# LCD_FRIDA.net
KiCad netlist of a schematic drawn in Altium Designer
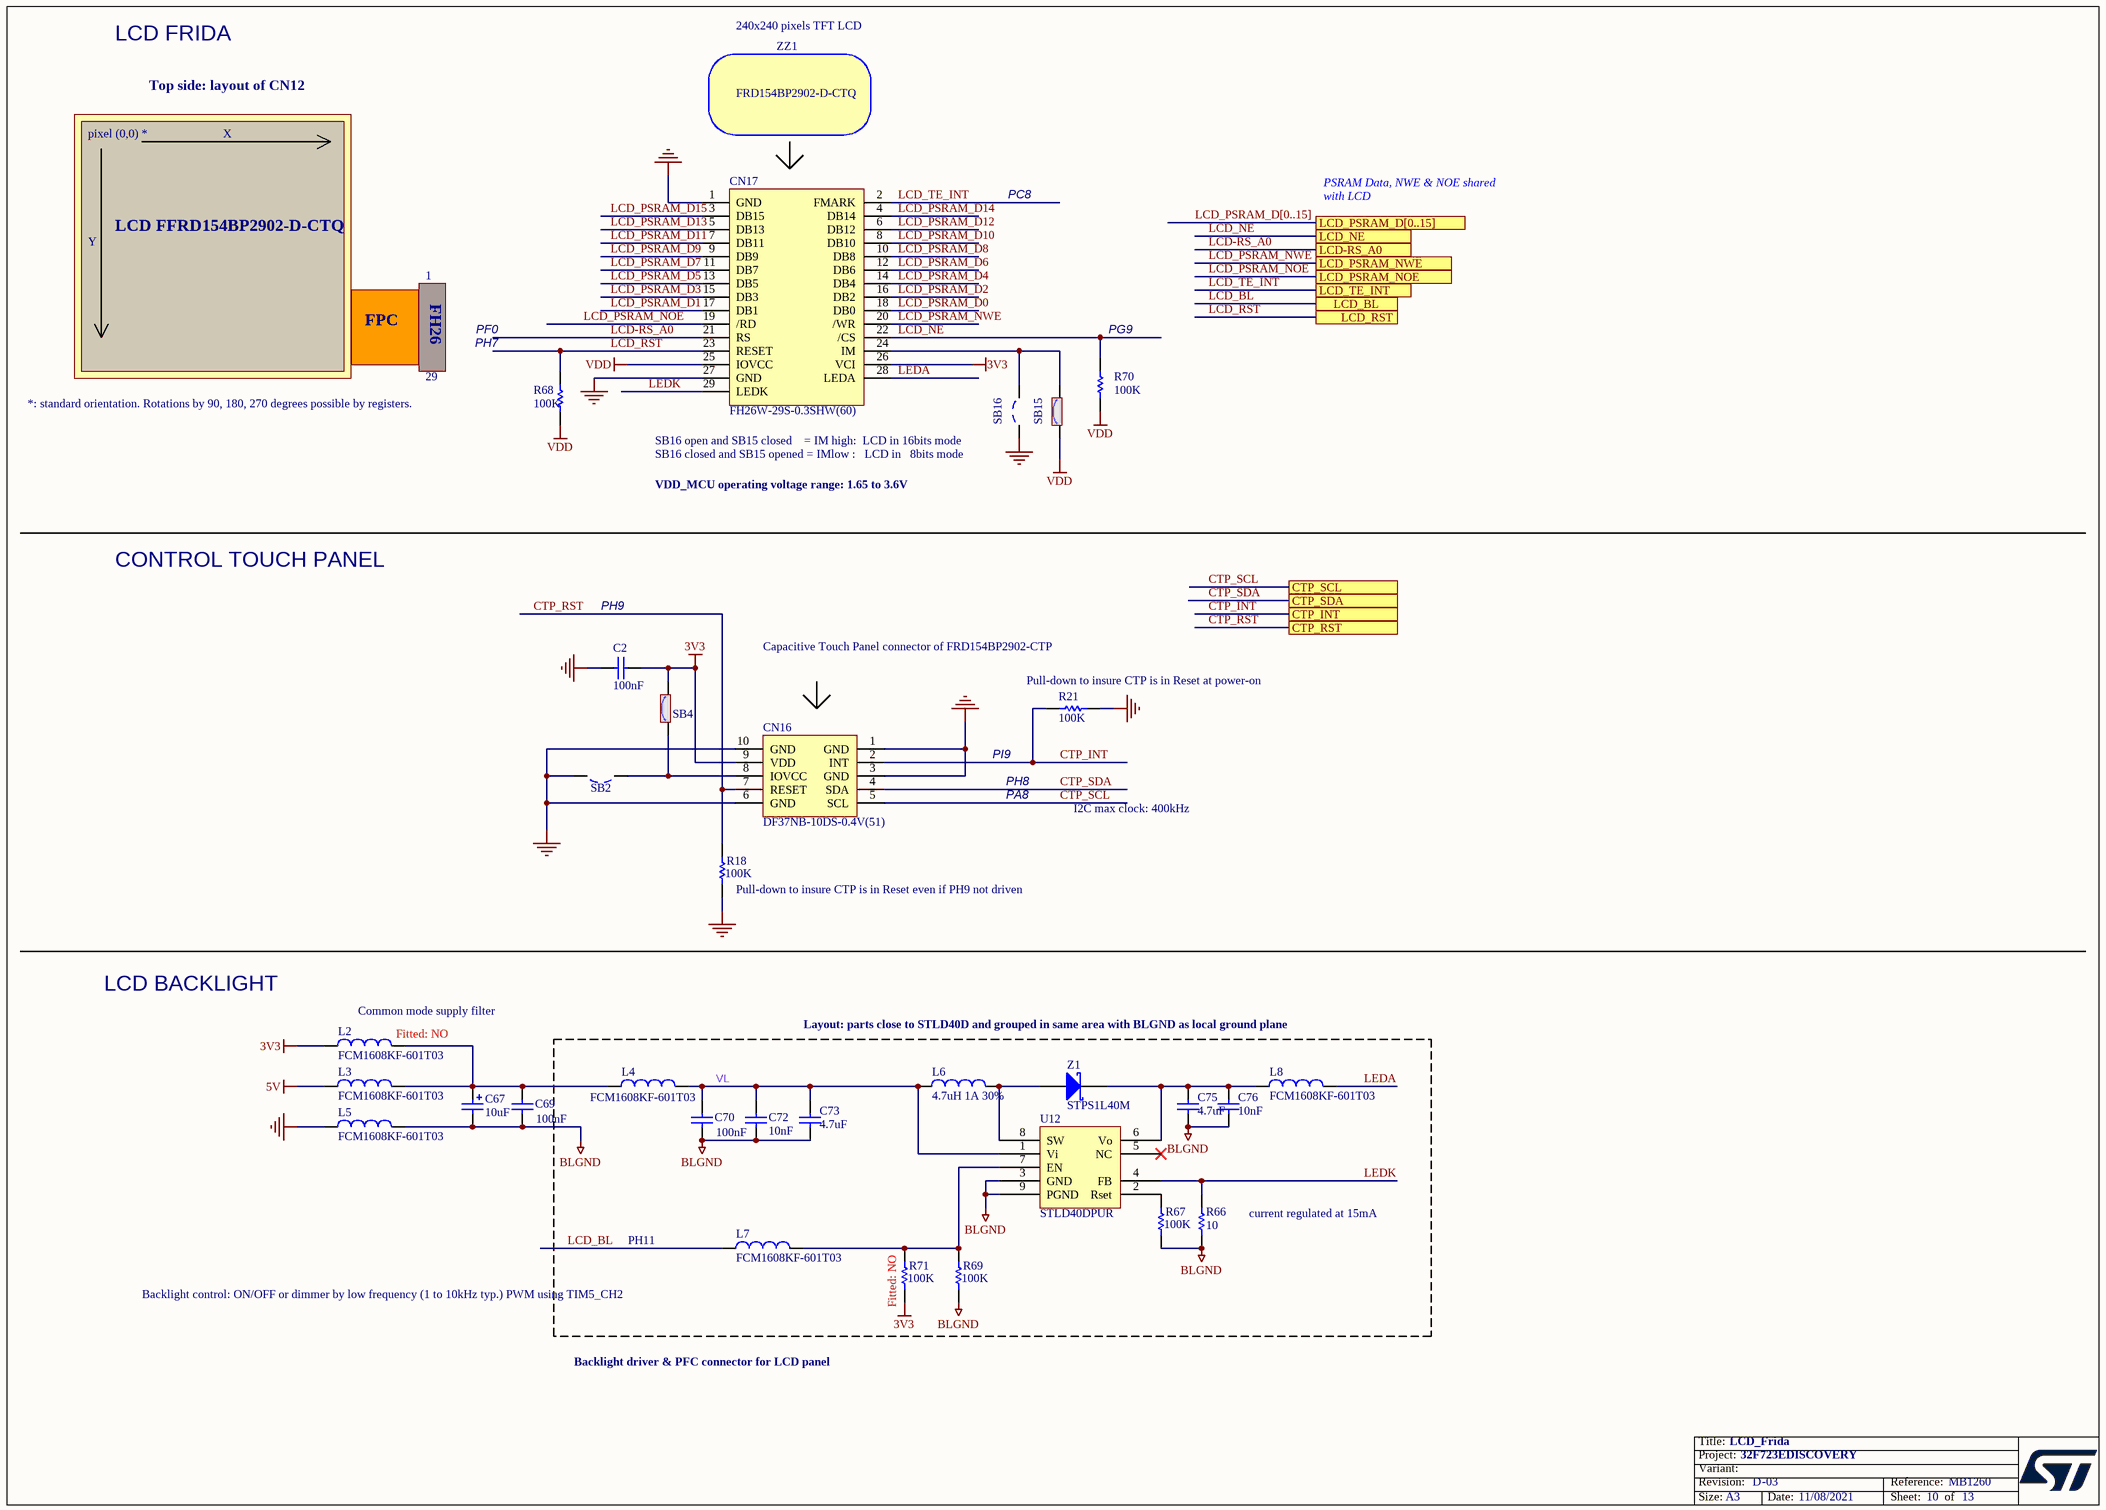
[diagram p0: LCD_FRIDA.SchDoc]

(export (version "E")
  (design (tool "Eeschema 10.0.6"))
  (components
    (comp (ref "C2")
      (value "100nF")
      (footprint "0402C")
      (description "Capacitor,100nF,16V,X7R,10%,0402,YAGEO")
      (libsource (lib "MCD_TOOLS") (part "Cap_100nF_X7R_10%_0402"))
    )
    (comp (ref "C67")
      (value "10uF")
      (footprint "TAN-A")
      (description "Polarized Capacitor,10uF,10V,10%,typeA,VISHAY")
      (fields (field (name "Comment") "10uF_POL_10%_TANA"))
      (libsource (lib "MCD_TOOLS_CAPACITOR") (part "Cap_10uF_POL_10%_TANA"))
    )
    (comp (ref "C69")
      (value "100nF")
      (footprint "0402C")
      (description "Capacitor,100nF,16V,X7R,10%,0402,YAGEO")
      (libsource (lib "MCD_TOOLS") (part "Cap_100nF_X7R_10%_0402"))
    )
    (comp (ref "C70")
      (value "100nF")
      (footprint "0402C")
      (description "Capacitor,100nF,16V,X7R,10%,0402,YAGEO")
      (libsource (lib "MCD_TOOLS") (part "Cap_100nF_X7R_10%_0402"))
    )
    (comp (ref "C72")
      (value "10nF")
      (footprint "0603C")
      (description "Capacitor,10nF,50V,X7R,10%,0603,YAGEO")
      (fields (field (name "Comment") "10nF_X7R_10%_0603"))
      (libsource (lib "MCD_TOOLS_CAPACITOR") (part "Cap_10nF_X7R_10%_0603"))
    )
    (comp (ref "C73")
      (value "4.7uF")
      (footprint "1206C")
      (description "Capacitor,4.7uF,50V, X7R,10%,1206,AVX")
      (fields (field (name "Comment") "4.7uF_X7R_10%_1206"))
      (libsource (lib "MCD_TOOLS_CAPACITOR") (part "Cap_4.7uF_X7R_10%_1206"))
    )
    (comp (ref "C75")
      (value "4.7uF")
      (footprint "1206C")
      (description "Capacitor,4.7uF,50V, X7R,10%,1206,AVX")
      (fields (field (name "Comment") "4.7uF_X7R_10%_1206"))
      (libsource (lib "MCD_TOOLS_CAPACITOR") (part "Cap_4.7uF_X7R_10%_1206"))
    )
    (comp (ref "C76")
      (value "10nF")
      (footprint "0603C")
      (description "Capacitor,10nF,50V,X7R,10%,0603,YAGEO")
      (fields (field (name "Comment") "10nF_X7R_10%_0603"))
      (libsource (lib "MCD_TOOLS_CAPACITOR") (part "Cap_10nF_X7R_10%_0603"))
    )
    (comp (ref "CN16")
      (value "DF37NB-10DS-0.4V(51)")
      (footprint "DF37NB-10DS-0R4V")
      (description "Header, 5-Pin, Dual row")
      (fields (field (name "PUBLISHER") "Altium Limited"))
      (libsource (lib "MB1209") (part "Header 5X2A"))
    )
    (comp (ref "CN17")
      (value "FH26W-29S-0.3SHW(60)")
      (footprint "FH26-29S-0R3SHW")
      (description "29pins FPC connector")
      (libsource (lib "MCD_TEMP_NPA") (part "FH26-29S-0.3SHW"))
    )
    (comp (ref "L2")
      (value "FCM1608KF-601T03")
      (footprint "0603L")
      (description "Bead,600R,350mA,0603,FCM1608KF-601T03,Tai-tech")
      (fields (field (name "FITTED") "NO"))
      (libsource (lib "MCD_TOOLS_MISCELLANEOUS") (part "BEAD_600R_350MA_0603"))
    )
    (comp (ref "L3")
      (value "FCM1608KF-601T03")
      (footprint "0603L")
      (description "Bead,600R,350mA,0603,FCM1608KF-601T03,Tai-tech")
      (libsource (lib "MCD_TOOLS_MISCELLANEOUS") (part "BEAD_600R_350MA_0603"))
    )
    (comp (ref "L4")
      (value "FCM1608KF-601T03")
      (footprint "0603L")
      (description "Bead,600R,350mA,0603,FCM1608KF-601T03,Tai-tech")
      (libsource (lib "MCD_TOOLS_MISCELLANEOUS") (part "BEAD_600R_350MA_0603"))
    )
    (comp (ref "L5")
      (value "FCM1608KF-601T03")
      (footprint "0603L")
      (description "Bead,600R,350mA,0603,FCM1608KF-601T03,Tai-tech")
      (libsource (lib "MCD_TOOLS_MISCELLANEOUS") (part "BEAD_600R_350MA_0603"))
    )
    (comp (ref "L6")
      (value "4.7uH 1A 30%")
      (footprint "1210L")
      (description "FIXED IND 4.7UH 1A 180 MOHM 30% SMD")
      (libsource (lib "MCD_TOOLS_MISCELLANEOUS") (part "Ind_4.7uH_1A_30%"))
    )
    (comp (ref "L7")
      (value "FCM1608KF-601T03")
      (footprint "0603L")
      (description "Bead,600R,350mA,0603,FCM1608KF-601T03,Tai-tech")
      (libsource (lib "MCD_TOOLS_MISCELLANEOUS") (part "BEAD_600R_350MA_0603"))
    )
    (comp (ref "L8")
      (value "FCM1608KF-601T03")
      (footprint "0603L")
      (description "Bead,600R,350mA,0603,FCM1608KF-601T03,Tai-tech")
      (libsource (lib "MCD_TOOLS_MISCELLANEOUS") (part "BEAD_600R_350MA_0603"))
    )
    (comp (ref "R18")
      (value "100K")
      (footprint "0402R")
      (description "Resistor,100K,0402,1%,YAGEO")
      (fields (field (name "Comment") "100K_1%_0402"))
      (libsource (lib "MCD_TOOLS_RESISTOR") (part "Res_100K_1%_0402"))
    )
    (comp (ref "R21")
      (value "100K")
      (footprint "0402R")
      (description "Resistor,100K,0402,1%,YAGEO")
      (fields (field (name "Comment") "100K_1%_0402"))
      (libsource (lib "MCD_TOOLS_RESISTOR") (part "Res_100K_1%_0402"))
    )
    (comp (ref "R66")
      (value "10")
      (footprint "0603R")
      (description "Resistor,10,0603,1%,ROHM,1/4W")
      (fields (field (name "Comment") "10_1%_0603"))
      (libsource (lib "MCD_TOOLS_RESISTOR") (part "Res_10_1%_0603"))
    )
    (comp (ref "R67")
      (value "100K")
      (footprint "0402R")
      (description "Resistor,100K,0402,1%,YAGEO")
      (fields (field (name "Comment") "100K_1%_0402"))
      (libsource (lib "MCD_TOOLS_RESISTOR") (part "Res_100K_1%_0402"))
    )
    (comp (ref "R68")
      (value "100K")
      (footprint "0402R")
      (description "Resistor,100K,0402,1%,YAGEO")
      (fields (field (name "Comment") "100K_1%_0402"))
      (libsource (lib "MCD_TOOLS_RESISTOR") (part "Res_100K_1%_0402"))
    )
    (comp (ref "R69")
      (value "100K")
      (footprint "0402R")
      (description "Resistor,100K,0402,1%,YAGEO")
      (fields (field (name "Comment") "100K_1%_0402"))
      (libsource (lib "MCD_TOOLS_RESISTOR") (part "Res_100K_1%_0402"))
    )
    (comp (ref "R70")
      (value "100K")
      (footprint "0402R")
      (description "Resistor,100K,0402,1%,YAGEO")
      (fields (field (name "Comment") "100K_1%_0402"))
      (libsource (lib "MCD_TOOLS_RESISTOR") (part "Res_100K_1%_0402"))
    )
    (comp (ref "R71")
      (value "100K")
      (footprint "0402R")
      (description "Resistor,100K,0402,1%,YAGEO")
      (fields (field (name "FITTED") "NO") (field (name "Comment") "100K_1%_0402"))
      (libsource (lib "MCD_TOOLS_RESISTOR") (part "Res_100K_1%_0402"))
    )
    (comp (ref "SB2")
      (value "Solder Bridge OFF")
      (footprint "JP2_SMD")
      (libsource (lib "MCD_TOOLS") (part "SB_OFF"))
    )
    (comp (ref "SB4")
      (value "Solder Bridge ON")
      (footprint "JP2_SMD")
      (libsource (lib "MCD_TOOLS") (part "SB_ON"))
    )
    (comp (ref "SB15")
      (value "Solder Bridge ON")
      (footprint "JP2_SMD")
      (libsource (lib "MCD_TOOLS") (part "SB_ON"))
    )
    (comp (ref "SB16")
      (value "Solder Bridge OFF")
      (footprint "JP2_SMD")
      (libsource (lib "MCD_TOOLS") (part "SB_OFF"))
    )
    (comp (ref "U12")
      (value "STLD40DPUR")
      (footprint "SON8_0R65_3X3")
      (description "White LED power supply for large display backlight")
      (libsource (lib "MCD_TEMP_NPA") (part "STLD40DPMR"))
    )
    (comp (ref "Z1")
      (value "STPS1L40M")
      (footprint "DO-216AA")
      (description "Schottky Diode")
      (fields (field (name "PUBLISHER") "Altium Limited"))
      (libsource (lib "Miscellaneous Devices") (part "D Schottky"))
    )
    (comp (ref "ZZ1")
      (value "FRD154BP2902-D-CTQ")
      (description "Frida LCD + Capacitive Touch Panel")
      (libsource (lib "Almos") (part "BoM_Item"))
    )
  )
  (nets
    (net (code "1") (name "/CTP_INT") (class "Default")
      (node (ref "CN16") (pin "2") (pinfunction "INT_2") (pintype "passive"))
      (node (ref "R21") (pin "2") (pinfunction "2_2") (pintype "passive"))
    )
    (net (code "2") (name "/CTP_RST") (class "Default")
      (node (ref "CN16") (pin "7") (pinfunction "RESET_7") (pintype "passive"))
      (node (ref "R18") (pin "2") (pinfunction "2_2") (pintype "passive"))
    )
    (net (code "3") (name "/CTP_SCL") (class "Default")
      (node (ref "CN16") (pin "5") (pinfunction "SCL_5") (pintype "passive"))
    )
    (net (code "4") (name "/CTP_SDA") (class "Default")
      (node (ref "CN16") (pin "4") (pinfunction "SDA_4") (pintype "passive"))
    )
    (net (code "5") (name "/LCD-RS_A0") (class "Default")
      (node (ref "CN17") (pin "21") (pinfunction "RS_21") (pintype "passive"))
    )
    (net (code "6") (name "/LCD_BL") (class "Default")
      (node (ref "L7") (pin "1") (pinfunction "1_1") (pintype "passive"))
    )
    (net (code "7") (name "/LCD_NE") (class "Default")
      (node (ref "CN17") (pin "22") (pinfunction "/CS_22") (pintype "passive"))
      (node (ref "R70") (pin "2") (pinfunction "2_2") (pintype "passive"))
    )
    (net (code "8") (name "/LCD_PSRAM_D0") (class "Default")
      (node (ref "CN17") (pin "18") (pinfunction "DB0_18") (pintype "passive"))
    )
    (net (code "9") (name "/LCD_PSRAM_D1") (class "Default")
      (node (ref "CN17") (pin "17") (pinfunction "DB1_17") (pintype "passive"))
    )
    (net (code "10") (name "/LCD_PSRAM_D2") (class "Default")
      (node (ref "CN17") (pin "16") (pinfunction "DB2_16") (pintype "passive"))
    )
    (net (code "11") (name "/LCD_PSRAM_D3") (class "Default")
      (node (ref "CN17") (pin "15") (pinfunction "DB3_15") (pintype "passive"))
    )
    (net (code "12") (name "/LCD_PSRAM_D4") (class "Default")
      (node (ref "CN17") (pin "14") (pinfunction "DB4_14") (pintype "passive"))
    )
    (net (code "13") (name "/LCD_PSRAM_D5") (class "Default")
      (node (ref "CN17") (pin "13") (pinfunction "DB5_13") (pintype "passive"))
    )
    (net (code "14") (name "/LCD_PSRAM_D6") (class "Default")
      (node (ref "CN17") (pin "12") (pinfunction "DB6_12") (pintype "passive"))
    )
    (net (code "15") (name "/LCD_PSRAM_D7") (class "Default")
      (node (ref "CN17") (pin "11") (pinfunction "DB7_11") (pintype "passive"))
    )
    (net (code "16") (name "/LCD_PSRAM_D8") (class "Default")
      (node (ref "CN17") (pin "10") (pinfunction "DB8_10") (pintype "passive"))
    )
    (net (code "17") (name "/LCD_PSRAM_D9") (class "Default")
      (node (ref "CN17") (pin "9") (pinfunction "DB9_9") (pintype "passive"))
    )
    (net (code "18") (name "/LCD_PSRAM_D10") (class "Default")
      (node (ref "CN17") (pin "8") (pinfunction "DB10_8") (pintype "passive"))
    )
    (net (code "19") (name "/LCD_PSRAM_D11") (class "Default")
      (node (ref "CN17") (pin "7") (pinfunction "DB11_7") (pintype "passive"))
    )
    (net (code "20") (name "/LCD_PSRAM_D12") (class "Default")
      (node (ref "CN17") (pin "6") (pinfunction "DB12_6") (pintype "passive"))
    )
    (net (code "21") (name "/LCD_PSRAM_D13") (class "Default")
      (node (ref "CN17") (pin "5") (pinfunction "DB13_5") (pintype "passive"))
    )
    (net (code "22") (name "/LCD_PSRAM_D14") (class "Default")
      (node (ref "CN17") (pin "4") (pinfunction "DB14_4") (pintype "passive"))
    )
    (net (code "23") (name "/LCD_PSRAM_D15") (class "Default")
      (node (ref "CN17") (pin "3") (pinfunction "DB15_3") (pintype "passive"))
    )
    (net (code "25") (name "/LCD_PSRAM_NOE") (class "Default")
      (node (ref "CN17") (pin "19") (pinfunction "/RD_19") (pintype "passive"))
    )
    (net (code "26") (name "/LCD_PSRAM_NWE") (class "Default")
      (node (ref "CN17") (pin "20") (pinfunction "/WR_20") (pintype "passive"))
    )
    (net (code "27") (name "/LCD_RST") (class "Default")
      (node (ref "CN17") (pin "23") (pinfunction "RESET_23") (pintype "passive"))
      (node (ref "R68") (pin "2") (pinfunction "2_2") (pintype "passive"))
    )
    (net (code "28") (name "/LCD_TE_INT") (class "Default")
      (node (ref "CN17") (pin "2") (pinfunction "FMARK_2") (pintype "passive"))
    )
    (net (code "29") (name "/LEDA") (class "Default")
      (node (ref "CN17") (pin "28") (pinfunction "LEDA_28") (pintype "passive"))
      (node (ref "L8") (pin "2") (pinfunction "2_2") (pintype "passive"))
    )
    (net (code "30") (name "/LEDK") (class "Default")
      (node (ref "CN17") (pin "29") (pinfunction "LEDK_29") (pintype "passive"))
      (node (ref "R66") (pin "2") (pinfunction "2_2") (pintype "passive"))
      (node (ref "U12") (pin "4") (pinfunction "FB_4") (pintype "passive"))
    )
    (net (code "31") (name "/VL") (class "Default")
      (node (ref "C70") (pin "2") (pinfunction "2_2") (pintype "passive"))
      (node (ref "C72") (pin "2") (pinfunction "2_2") (pintype "passive"))
      (node (ref "C73") (pin "2") (pinfunction "2_2") (pintype "passive"))
      (node (ref "L4") (pin "2") (pinfunction "2_2") (pintype "passive"))
      (node (ref "L6") (pin "1") (pinfunction "1_1") (pintype "passive"))
      (node (ref "U12") (pin "1") (pinfunction "Vi_1") (pintype "passive"))
    )
    (net (code "32") (name "3V3") (class "Default")
      (node (ref "C2") (pin "1") (pinfunction "1_1") (pintype "passive"))
      (node (ref "CN16") (pin "9") (pinfunction "VDD_9") (pintype "passive"))
      (node (ref "CN17") (pin "26") (pinfunction "VCI_26") (pintype "passive"))
      (node (ref "L2") (pin "1") (pinfunction "1_1") (pintype "passive"))
      (node (ref "R71") (pin "1") (pinfunction "1_1") (pintype "passive"))
      (node (ref "SB4") (pin "2") (pinfunction "2_2") (pintype "passive"))
    )
    (net (code "33") (name "5V") (class "Default")
      (node (ref "L3") (pin "1") (pinfunction "1_1") (pintype "passive"))
    )
    (net (code "34") (name "BLGND") (class "Default")
      (node (ref "C67") (pin "2") (pinfunction "2_2") (pintype "passive"))
      (node (ref "C69") (pin "1") (pinfunction "1_1") (pintype "passive"))
      (node (ref "C70") (pin "1") (pinfunction "1_1") (pintype "passive"))
      (node (ref "C72") (pin "1") (pinfunction "1_1") (pintype "passive"))
      (node (ref "C73") (pin "1") (pinfunction "1_1") (pintype "passive"))
      (node (ref "C75") (pin "1") (pinfunction "1_1") (pintype "passive"))
      (node (ref "C76") (pin "1") (pinfunction "1_1") (pintype "passive"))
      (node (ref "L5") (pin "2") (pinfunction "2_2") (pintype "passive"))
      (node (ref "R66") (pin "1") (pinfunction "1_1") (pintype "passive"))
      (node (ref "R67") (pin "1") (pinfunction "1_1") (pintype "passive"))
      (node (ref "R69") (pin "1") (pinfunction "1_1") (pintype "passive"))
      (node (ref "U12") (pin "3") (pinfunction "GND_3") (pintype "passive"))
      (node (ref "U12") (pin "9") (pinfunction "PGND_9") (pintype "passive"))
    )
    (net (code "35") (name "GND") (class "Default")
      (node (ref "C2") (pin "2") (pinfunction "2_2") (pintype "passive"))
      (node (ref "CN16") (pin "1") (pinfunction "GND_1") (pintype "passive"))
      (node (ref "CN16") (pin "10") (pinfunction "GND_10") (pintype "passive"))
      (node (ref "CN16") (pin "3") (pinfunction "GND_3") (pintype "passive"))
      (node (ref "CN16") (pin "6") (pinfunction "GND_6") (pintype "passive"))
      (node (ref "CN17") (pin "1") (pinfunction "GND_1") (pintype "passive"))
      (node (ref "CN17") (pin "27") (pinfunction "GND_27") (pintype "passive"))
      (node (ref "L5") (pin "1") (pinfunction "1_1") (pintype "passive"))
      (node (ref "R18") (pin "1") (pinfunction "1_1") (pintype "passive"))
      (node (ref "R21") (pin "1") (pinfunction "1_1") (pintype "passive"))
      (node (ref "SB16") (pin "1") (pinfunction "1_1") (pintype "passive"))
      (node (ref "SB2") (pin "2") (pinfunction "2_2") (pintype "passive"))
    )
    (net (code "36") (name "Net-(C67-Pad1)") (class "Default")
      (node (ref "C67") (pin "1") (pinfunction "1_1") (pintype "passive"))
      (node (ref "C69") (pin "2") (pinfunction "2_2") (pintype "passive"))
      (node (ref "L2") (pin "2") (pinfunction "2_2") (pintype "passive"))
      (node (ref "L3") (pin "2") (pinfunction "2_2") (pintype "passive"))
      (node (ref "L4") (pin "1") (pinfunction "1_1") (pintype "passive"))
    )
    (net (code "37") (name "Net-(CN16-IOVCC)") (class "Default")
      (node (ref "CN16") (pin "8") (pinfunction "IOVCC_8") (pintype "passive"))
      (node (ref "SB2") (pin "1") (pinfunction "1_1") (pintype "passive"))
      (node (ref "SB4") (pin "1") (pinfunction "1_1") (pintype "passive"))
    )
    (net (code "38") (name "Net-(CN17-IM)") (class "Default")
      (node (ref "CN17") (pin "24") (pinfunction "IM_24") (pintype "passive"))
      (node (ref "SB15") (pin "2") (pinfunction "2_2") (pintype "passive"))
      (node (ref "SB16") (pin "2") (pinfunction "2_2") (pintype "passive"))
    )
    (net (code "39") (name "Net-(U12-EN)") (class "Default")
      (node (ref "L7") (pin "2") (pinfunction "2_2") (pintype "passive"))
      (node (ref "R69") (pin "2") (pinfunction "2_2") (pintype "passive"))
      (node (ref "R71") (pin "2") (pinfunction "2_2") (pintype "passive"))
      (node (ref "U12") (pin "7") (pinfunction "EN_7") (pintype "passive"))
    )
    (net (code "40") (name "Net-(U12-Rset)") (class "Default")
      (node (ref "R67") (pin "2") (pinfunction "2_2") (pintype "passive"))
      (node (ref "U12") (pin "2") (pinfunction "Rset_2") (pintype "passive"))
    )
    (net (code "41") (name "Net-(U12-SW)") (class "Default")
      (node (ref "L6") (pin "2") (pinfunction "2_2") (pintype "passive"))
      (node (ref "U12") (pin "8") (pinfunction "SW_8") (pintype "passive"))
      (node (ref "Z1") (pin "1") (pinfunction "A_1") (pintype "passive"))
    )
    (net (code "42") (name "Net-(U12-Vo)") (class "Default")
      (node (ref "C75") (pin "2") (pinfunction "2_2") (pintype "passive"))
      (node (ref "C76") (pin "2") (pinfunction "2_2") (pintype "passive"))
      (node (ref "L8") (pin "1") (pinfunction "1_1") (pintype "passive"))
      (node (ref "U12") (pin "6") (pinfunction "Vo_6") (pintype "passive"))
      (node (ref "Z1") (pin "2") (pinfunction "K_2") (pintype "passive"))
    )
    (net (code "43") (name "VDD") (class "Default")
      (node (ref "CN17") (pin "25") (pinfunction "IOVCC_25") (pintype "passive"))
      (node (ref "R68") (pin "1") (pinfunction "1_1") (pintype "passive"))
      (node (ref "R70") (pin "1") (pinfunction "1_1") (pintype "passive"))
      (node (ref "SB15") (pin "1") (pinfunction "1_1") (pintype "passive"))
    )
    (net (code "44") (name "unconnected-(U12-NC-Pad5)") (class "Default")
      (node (ref "U12") (pin "5") (pinfunction "NC_5") (pintype "passive+no_connect"))
    )
  )
)
